# CON_PCPPORT_26WBOXHDRRAM.net
KiCad netlist of a schematic drawn in Altium Designer
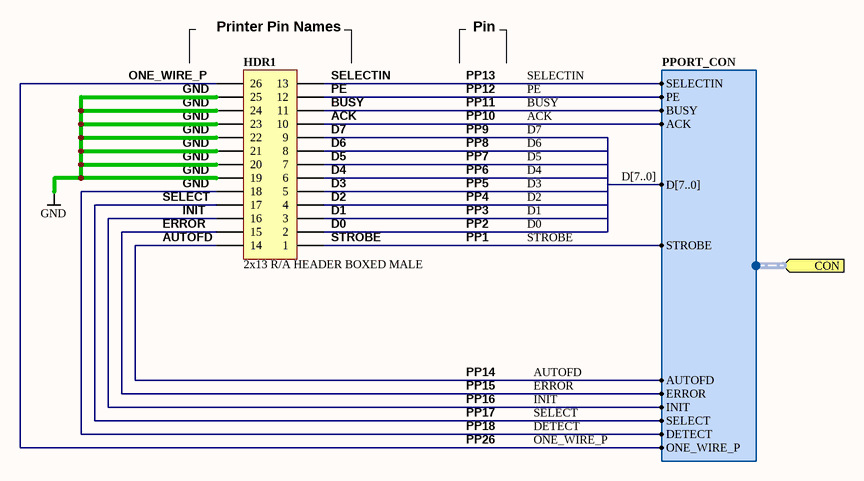
[diagram p0: CON_PCPPORT_26WBOXHDRRAM.SchDoc]

(export (version "E")
  (design (tool "Eeschema 10.0.6"))
  (components
    (comp (ref "HDR1")
      (value "2x13 R/A HEADER BOXED MALE")
      (footprint "HDR2X13_RA_CENTRONICS")
      (description "Header IDC, 2 x 13 Pin Right-Angle 2.54mm Pitch (Boxed-Male)")
      (libsource (lib "altium-import") (part "root_2_CON-IDC-2x13-M-RA_"))
    )
  )
  (nets
    (net (code "2") (name "/ACK") (class "Default")
      (node (ref "HDR1") (pin "10") (pinfunction "10_10") (pintype "passive"))
    )
    (net (code "3") (name "/AUTOFD") (class "Default")
      (node (ref "HDR1") (pin "14") (pinfunction "14_14") (pintype "passive"))
    )
    (net (code "4") (name "/BUSY") (class "Default")
      (node (ref "HDR1") (pin "11") (pinfunction "11_11") (pintype "passive"))
    )
    (net (code "5") (name "/D0") (class "Default")
      (node (ref "HDR1") (pin "2") (pinfunction "2_2") (pintype "passive"))
    )
    (net (code "6") (name "/D1") (class "Default")
      (node (ref "HDR1") (pin "3") (pinfunction "3_3") (pintype "passive"))
    )
    (net (code "7") (name "/D2") (class "Default")
      (node (ref "HDR1") (pin "4") (pinfunction "4_4") (pintype "passive"))
    )
    (net (code "8") (name "/D3") (class "Default")
      (node (ref "HDR1") (pin "5") (pinfunction "5_5") (pintype "passive"))
    )
    (net (code "9") (name "/D4") (class "Default")
      (node (ref "HDR1") (pin "6") (pinfunction "6_6") (pintype "passive"))
    )
    (net (code "10") (name "/D5") (class "Default")
      (node (ref "HDR1") (pin "7") (pinfunction "7_7") (pintype "passive"))
    )
    (net (code "11") (name "/D6") (class "Default")
      (node (ref "HDR1") (pin "8") (pinfunction "8_8") (pintype "passive"))
    )
    (net (code "12") (name "/D7") (class "Default")
      (node (ref "HDR1") (pin "9") (pinfunction "9_9") (pintype "passive"))
    )
    (net (code "13") (name "/DETECT") (class "Default")
      (node (ref "HDR1") (pin "18") (pinfunction "18_18") (pintype "passive"))
    )
    (net (code "15") (name "/ERROR") (class "Default")
      (node (ref "HDR1") (pin "15") (pinfunction "15_15") (pintype "passive"))
    )
    (net (code "16") (name "/INIT") (class "Default")
      (node (ref "HDR1") (pin "16") (pinfunction "16_16") (pintype "passive"))
    )
    (net (code "17") (name "/ONE_WIRE_P") (class "Default")
      (node (ref "HDR1") (pin "26") (pinfunction "26_26") (pintype "passive"))
    )
    (net (code "18") (name "/PE") (class "Default")
      (node (ref "HDR1") (pin "12") (pinfunction "12_12") (pintype "passive"))
    )
    (net (code "19") (name "/SELECT") (class "Default")
      (node (ref "HDR1") (pin "17") (pinfunction "17_17") (pintype "passive"))
    )
    (net (code "20") (name "/SELECTIN") (class "Default")
      (node (ref "HDR1") (pin "13") (pinfunction "13_13") (pintype "passive"))
    )
    (net (code "21") (name "/STROBE") (class "Default")
      (node (ref "HDR1") (pin "1") (pinfunction "1_1") (pintype "passive"))
    )
    (net (code "23") (name "GND") (class "Default")
      (node (ref "HDR1") (pin "19") (pinfunction "19_19") (pintype "passive"))
      (node (ref "HDR1") (pin "20") (pinfunction "20_20") (pintype "passive"))
      (node (ref "HDR1") (pin "21") (pinfunction "21_21") (pintype "passive"))
      (node (ref "HDR1") (pin "22") (pinfunction "22_22") (pintype "passive"))
      (node (ref "HDR1") (pin "23") (pinfunction "23_23") (pintype "passive"))
      (node (ref "HDR1") (pin "24") (pinfunction "24_24") (pintype "passive"))
      (node (ref "HDR1") (pin "25") (pinfunction "25_25") (pintype "passive"))
    )
  )
)
